# Neopixel_Driver.net
KiCad netlist of a schematic drawn in Altium Designer
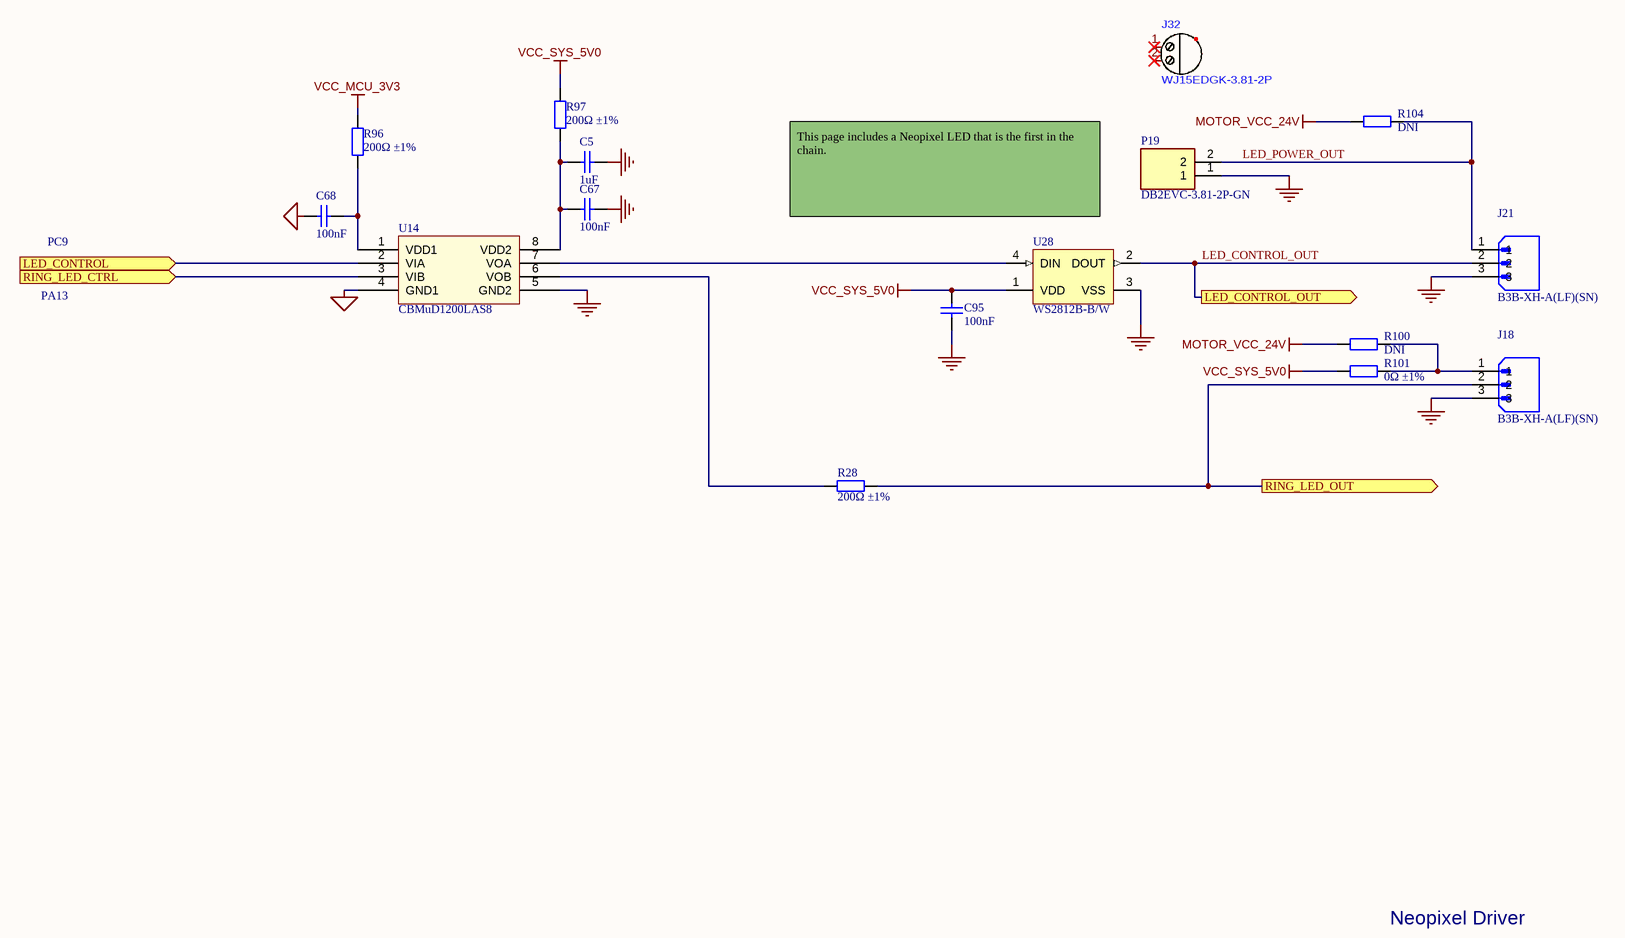
[diagram p0: Neopixel_Driver.SchDoc]

(export (version "E")
  (design (tool "Eeschema 10.0.6"))
  (components
    (comp (ref "C5")
      (value "1uF")
      (footprint "0603_C")
      (description "Chip capacitors")
      (fields (field (name "MANUFACTURER") "Samsung Electro-Mechanics") (field (name "TOLERANCE") "10%"))
      (libsource (lib "Sienci_Labs") (part "0603 1uF (105) 10% 50V"))
    )
    (comp (ref "C67")
      (value "100nF")
      (footprint "0603_C")
      (description "50V 100nF X7R ±10% 0603 Multilayer Ceramic Capacitors MLCC - SMD/SMT ROHS")
      (fields (field (name "MANUFACTURER") "YAGEO") (field (name "TOLERANCE") "10%"))
      (libsource (lib "Sienci_Labs") (part "0603 100nF (104) 10% 50V"))
    )
    (comp (ref "C68")
      (value "100nF")
      (footprint "0603_C")
      (description "50V 100nF X7R ±10% 0603 Multilayer Ceramic Capacitors MLCC - SMD/SMT ROHS")
      (fields (field (name "MANUFACTURER") "YAGEO") (field (name "TOLERANCE") "10%"))
      (libsource (lib "Sienci_Labs") (part "0603 100nF (104) 10% 50V"))
    )
    (comp (ref "C95")
      (value "100nF")
      (footprint "0603_C")
      (description "50V 100nF X7R ±10% 0603 Multilayer Ceramic Capacitors MLCC - SMD/SMT ROHS")
      (fields
        (field (name "MANUFACTURER") "YAGEO")
        (field (name "MANUFACTURER PART NUMBER") "CC0603KRX7R9BB104")
      )
      (libsource (lib "Sienci_Labs") (part "0603 100nF (104) 10% 50V"))
    )
    (comp (ref "J18")
      (value "B3B-XH-A(LF)(SN)")
      (footprint "JST_B3B-XH-A(LF)(SN)")
      (description "Connector Header Through Hole 3 position 0.098\" (2.50mm)")
      (fields (field (name "MANUFACTURER") "JST Sales America"))
      (libsource (lib "Sienci_Labs") (part "B3B-XH-A(LF)(SN)"))
    )
    (comp (ref "J21")
      (value "B3B-XH-A(LF)(SN)")
      (footprint "JST_B3B-XH-A(LF)(SN)")
      (description "Connector Header Through Hole 3 position 0.098\" (2.50mm)")
      (fields (field (name "MANUFACTURER") "JST Sales America"))
      (libsource (lib "Sienci_Labs") (part "B3B-XH-A(LF)(SN)"))
    )
    (comp (ref "J32")
      (value "WJ15EDGK-3.81-2P")
      (description "2 1 3.81mm Green Plug P=3.81mm Pluggable System Terminal Block ROHS")
      (fields (field (name "MANUFACTURER") "Ningbo"))
      (libsource (lib "Sienci_Labs") (part "WJ15EDGK-3.81-2P"))
    )
    (comp (ref "P19")
      (value "DB2EVC-3.81-2P-GN")
      (footprint "CONN-TH_5P-P3.81_DB2EVC-3.81-2p")
      (description "3.81mm Green Board Edge/Receptacle-Close Push-Pull,P=3.81mm Pluggable System Terminal Block ROHS")
      (fields (field (name "MANUFACTURER") "DIBO"))
      (libsource (lib "Sienci_Labs") (part "DB2EVC-3.81-2P-GN"))
    )
    (comp (ref "R28")
      (value "200Ω ±1%")
      (footprint "0402_R")
      (description "Chip resistor")
      (fields
        (field (name "MANUFACTURER") "Uniroyal Elec")
        (field (name "MANUFACTURER PART NUMBER") "0402WGF2000TCE")
      )
      (libsource (lib "") (part "0402 200R (2000) 1%_1"))
    )
    (comp (ref "R96")
      (value "200Ω ±1%")
      (footprint "0402_R")
      (description "Chip resistor")
      (fields
        (field (name "MANUFACTURER") "Uniroyal Elec")
        (field (name "MANUFACTURER PART NUMBER") "0402WGF2000TCE")
      )
      (libsource (lib "RES") (part "0402 200R (2000) 1%"))
    )
    (comp (ref "R97")
      (value "200Ω ±1%")
      (footprint "0402_R")
      (description "Chip resistor")
      (fields
        (field (name "MANUFACTURER") "Uniroyal Elec")
        (field (name "MANUFACTURER PART NUMBER") "0402WGF2000TCE")
      )
      (libsource (lib "RES") (part "0402 200R (2000) 1%"))
    )
    (comp (ref "R100")
      (value "DNI")
      (footprint "0603_R")
      (description "Chip resistor")
      (fields
        (field (name "MANUFACTURER") "Uniroyal Elec")
        (field (name "MANUFACTURER PART NUMBER") "0603WAF0000T5E")
      )
      (libsource (lib "RES") (part "0603 0R (0R0) 1%"))
    )
    (comp (ref "R101")
      (value "0Ω ±1%")
      (footprint "0603_R")
      (description "Chip resistor")
      (fields
        (field (name "MANUFACTURER") "Uniroyal Elec")
        (field (name "MANUFACTURER PART NUMBER") "0603WAF0000T5E")
      )
      (libsource (lib "RES") (part "0603 0R (0R0) 1%"))
    )
    (comp (ref "R104")
      (value "DNI")
      (footprint "0805_R")
      (description "Chip resistor")
      (fields (field (name "MANUFACTURER") "Uniroyal Elec") (field (name "POWER") "1/8W"))
      (libsource (lib "RES") (part "0805 0R (0R0) 1%"))
    )
    (comp (ref "U14")
      (value "CBMuD1200LAS8")
      (footprint "SOIC-8_150mil")
      (description "Dual Channel Isolator")
      (fields (field (name "MANUFACTURER") "Corebai Microelectronics"))
      (libsource (lib "Sienci_Labs") (part "CBMuD1200LAS8"))
    )
    (comp (ref "U28")
      (value "WS2812B-B/W")
      (footprint "ADA-RGB-1655_V")
      (fields (field (name "MANUFACTURER") "Worldsemi"))
      (libsource (lib "Sienci_Labs") (part "WS2812B-B/W"))
    )
  )
  (nets
    (net (code "1") (name "/LED_CONTROL") (class "Default")
      (node (ref "U14") (pin "2") (pinfunction "VIA_2") (pintype "passive"))
    )
    (net (code "2") (name "/LED_CONTROL_OUT") (class "Default")
      (node (ref "J21") (pin "2") (pinfunction "2_2") (pintype "passive"))
      (node (ref "U28") (pin "2") (pinfunction "DOUT_2") (pintype "output"))
    )
    (net (code "3") (name "/LED_POWER_OUT") (class "Default")
      (node (ref "J21") (pin "1") (pinfunction "1_1") (pintype "passive"))
      (node (ref "P19") (pin "2") (pinfunction "2_2") (pintype "passive"))
      (node (ref "R104") (pin "1") (pinfunction "1_1") (pintype "passive"))
    )
    (net (code "4") (name "/RING_LED_CTRL") (class "Default")
      (node (ref "U14") (pin "3") (pinfunction "VIB_3") (pintype "passive"))
    )
    (net (code "5") (name "/RING_LED_OUT") (class "Default")
      (node (ref "J18") (pin "2") (pinfunction "2_2") (pintype "passive"))
      (node (ref "R28") (pin "1") (pinfunction "1_1") (pintype "passive"))
    )
    (net (code "6") (name "GND") (class "Default")
      (node (ref "C5") (pin "1") (pinfunction "1_1") (pintype "passive"))
      (node (ref "C67") (pin "1") (pinfunction "1_1") (pintype "passive"))
      (node (ref "C95") (pin "1") (pinfunction "1_1") (pintype "passive"))
      (node (ref "J18") (pin "3") (pinfunction "3_3") (pintype "passive"))
      (node (ref "J21") (pin "3") (pinfunction "3_3") (pintype "passive"))
      (node (ref "P19") (pin "1") (pinfunction "1_1") (pintype "passive"))
      (node (ref "U14") (pin "5") (pinfunction "GND2_5") (pintype "passive"))
      (node (ref "U28") (pin "3") (pinfunction "VSS_3") (pintype "power_in"))
    )
    (net (code "7") (name "MCU_GND") (class "Default")
      (node (ref "C68") (pin "2") (pinfunction "2_2") (pintype "passive"))
      (node (ref "U14") (pin "4") (pinfunction "GND1_4") (pintype "passive"))
    )
    (net (code "8") (name "MOTOR_VCC_24V") (class "Default")
      (node (ref "R100") (pin "2") (pinfunction "2_2") (pintype "passive"))
      (node (ref "R104") (pin "2") (pinfunction "2_2") (pintype "passive"))
    )
    (net (code "9") (name "Net-(J18-Pad1)") (class "Default")
      (node (ref "J18") (pin "1") (pinfunction "1_1") (pintype "passive"))
      (node (ref "R100") (pin "1") (pinfunction "1_1") (pintype "passive"))
      (node (ref "R101") (pin "1") (pinfunction "1_1") (pintype "passive"))
    )
    (net (code "10") (name "Net-(U14-VDD1)") (class "Default")
      (node (ref "C68") (pin "1") (pinfunction "1_1") (pintype "passive"))
      (node (ref "R96") (pin "1") (pinfunction "1_1") (pintype "passive"))
      (node (ref "U14") (pin "1") (pinfunction "VDD1_1") (pintype "passive"))
    )
    (net (code "11") (name "Net-(U14-VDD2)") (class "Default")
      (node (ref "C5") (pin "2") (pinfunction "2_2") (pintype "passive"))
      (node (ref "C67") (pin "2") (pinfunction "2_2") (pintype "passive"))
      (node (ref "R97") (pin "1") (pinfunction "1_1") (pintype "passive"))
      (node (ref "U14") (pin "8") (pinfunction "VDD2_8") (pintype "passive"))
    )
    (net (code "12") (name "Net-(U14-VOA)") (class "Default")
      (node (ref "U14") (pin "7") (pinfunction "VOA_7") (pintype "passive"))
      (node (ref "U28") (pin "4") (pinfunction "DIN_4") (pintype "input"))
    )
    (net (code "13") (name "Net-(U14-VOB)") (class "Default")
      (node (ref "R28") (pin "2") (pinfunction "2_2") (pintype "passive"))
      (node (ref "U14") (pin "6") (pinfunction "VOB_6") (pintype "passive"))
    )
    (net (code "14") (name "VCC_MCU_3V3") (class "Default")
      (node (ref "R96") (pin "2") (pinfunction "2_2") (pintype "passive"))
    )
    (net (code "15") (name "VCC_SYS_5V0") (class "Default")
      (node (ref "C95") (pin "2") (pinfunction "2_2") (pintype "passive"))
      (node (ref "R101") (pin "2") (pinfunction "2_2") (pintype "passive"))
      (node (ref "R97") (pin "2") (pinfunction "2_2") (pintype "passive"))
      (node (ref "U28") (pin "1") (pinfunction "VDD_1") (pintype "power_in"))
    )
    (net (code "16") (name "unconnected-(J32-Pad1)") (class "Default")
      (node (ref "J32") (pin "1") (pinfunction "1_1") (pintype "passive+no_connect"))
    )
    (net (code "17") (name "unconnected-(J32-Pad2)") (class "Default")
      (node (ref "J32") (pin "2") (pinfunction "2_2") (pintype "passive+no_connect"))
    )
  )
)
